# jeu_du_moulin_boura_LedMatrix_SCH.net
KiCad netlist of a schematic drawn in Altium Designer
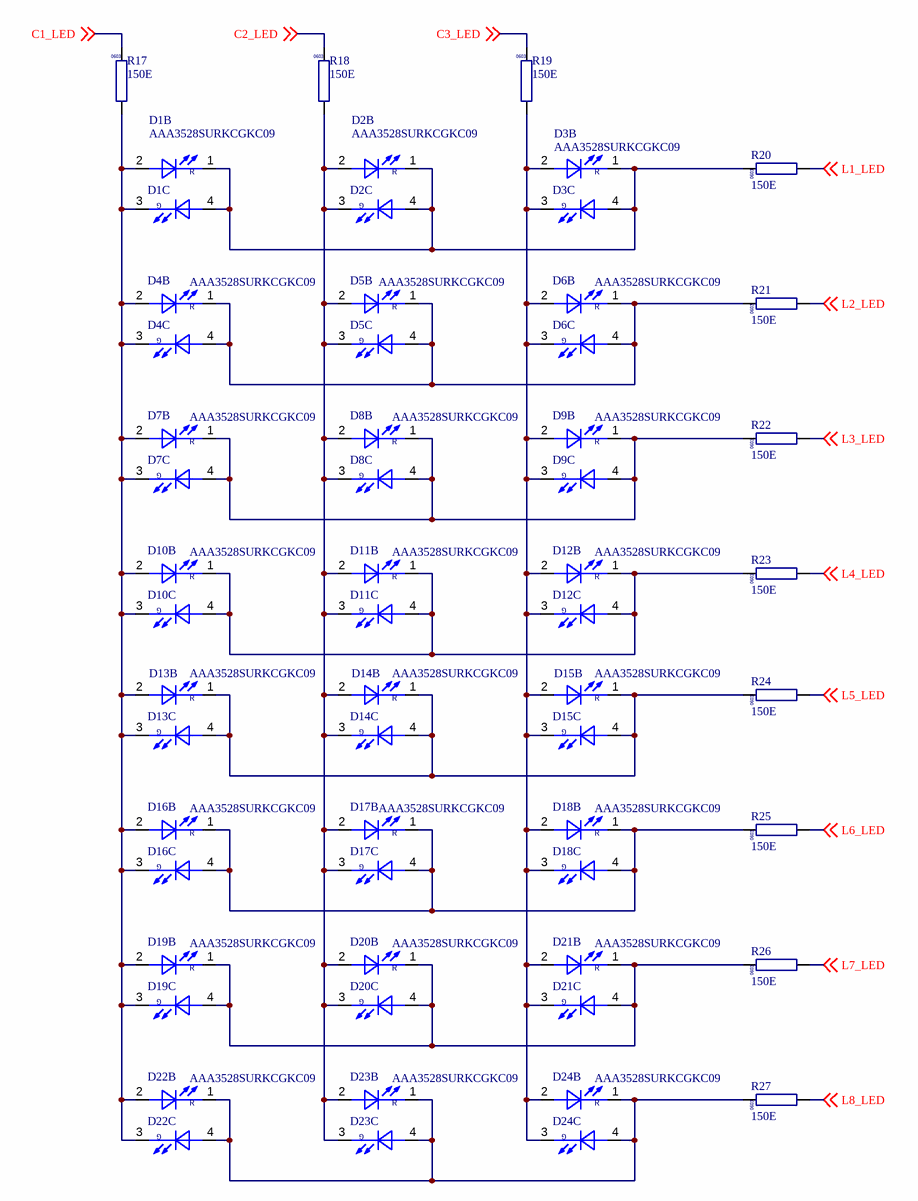
[diagram p0: jeu_du_moulin_boura_LedMatrix_SCH.SchDoc]

(export (version "E")
  (design (tool "Eeschema 10.0.6"))
  (components
    (comp (ref "D1")
      (value "AAA3528SURKCGKC09")
      (footprint "TouchPAD-8mm+LED 4-SMD CIR")
      (libsource (lib "jeu_du_moulin_boura_INTLIB") (part "TouchPAD-BILED4SMD"))
    )
    (comp (ref "D2")
      (value "AAA3528SURKCGKC09")
      (footprint "TouchPAD-8mm+LED 4-SMD CIR")
      (libsource (lib "jeu_du_moulin_boura_INTLIB") (part "TouchPAD-BILED4SMD"))
    )
    (comp (ref "D3")
      (value "AAA3528SURKCGKC09")
      (footprint "TouchPAD-8mm+LED 4-SMD CIR")
      (libsource (lib "jeu_du_moulin_boura_INTLIB") (part "TouchPAD-BILED4SMD"))
    )
    (comp (ref "D4")
      (value "AAA3528SURKCGKC09")
      (footprint "TouchPAD-8mm+LED 4-SMD CIR")
      (libsource (lib "jeu_du_moulin_boura_INTLIB") (part "TouchPAD-BILED4SMD"))
    )
    (comp (ref "D5")
      (value "AAA3528SURKCGKC09")
      (footprint "TouchPAD-8mm+LED 4-SMD CIR")
      (libsource (lib "jeu_du_moulin_boura_INTLIB") (part "TouchPAD-BILED4SMD"))
    )
    (comp (ref "D6")
      (value "AAA3528SURKCGKC09")
      (footprint "TouchPAD-8mm+LED 4-SMD CIR")
      (libsource (lib "jeu_du_moulin_boura_INTLIB") (part "TouchPAD-BILED4SMD"))
    )
    (comp (ref "D7")
      (value "AAA3528SURKCGKC09")
      (footprint "TouchPAD-8mm+LED 4-SMD CIR")
      (libsource (lib "jeu_du_moulin_boura_INTLIB") (part "TouchPAD-BILED4SMD"))
    )
    (comp (ref "D8")
      (value "AAA3528SURKCGKC09")
      (footprint "TouchPAD-8mm+LED 4-SMD CIR")
      (libsource (lib "jeu_du_moulin_boura_INTLIB") (part "TouchPAD-BILED4SMD"))
    )
    (comp (ref "D9")
      (value "AAA3528SURKCGKC09")
      (footprint "TouchPAD-8mm+LED 4-SMD CIR")
      (libsource (lib "jeu_du_moulin_boura_INTLIB") (part "TouchPAD-BILED4SMD"))
    )
    (comp (ref "D10")
      (value "AAA3528SURKCGKC09")
      (footprint "TouchPAD-8mm+LED 4-SMD CIR")
      (libsource (lib "jeu_du_moulin_boura_INTLIB") (part "TouchPAD-BILED4SMD"))
    )
    (comp (ref "D11")
      (value "AAA3528SURKCGKC09")
      (footprint "TouchPAD-8mm+LED 4-SMD CIR")
      (libsource (lib "jeu_du_moulin_boura_INTLIB") (part "TouchPAD-BILED4SMD"))
    )
    (comp (ref "D12")
      (value "AAA3528SURKCGKC09")
      (footprint "TouchPAD-8mm+LED 4-SMD CIR")
      (libsource (lib "jeu_du_moulin_boura_INTLIB") (part "TouchPAD-BILED4SMD"))
    )
    (comp (ref "D13")
      (value "AAA3528SURKCGKC09")
      (footprint "TouchPAD-8mm+LED 4-SMD CIR")
      (libsource (lib "jeu_du_moulin_boura_INTLIB") (part "TouchPAD-BILED4SMD"))
    )
    (comp (ref "D14")
      (value "AAA3528SURKCGKC09")
      (footprint "TouchPAD-8mm+LED 4-SMD CIR")
      (libsource (lib "jeu_du_moulin_boura_INTLIB") (part "TouchPAD-BILED4SMD"))
    )
    (comp (ref "D15")
      (value "AAA3528SURKCGKC09")
      (footprint "TouchPAD-8mm+LED 4-SMD CIR")
      (libsource (lib "jeu_du_moulin_boura_INTLIB") (part "TouchPAD-BILED4SMD"))
    )
    (comp (ref "D16")
      (value "AAA3528SURKCGKC09")
      (footprint "TouchPAD-8mm+LED 4-SMD CIR")
      (libsource (lib "jeu_du_moulin_boura_INTLIB") (part "TouchPAD-BILED4SMD"))
    )
    (comp (ref "D17")
      (value "AAA3528SURKCGKC09")
      (footprint "TouchPAD-8mm+LED 4-SMD CIR")
      (libsource (lib "jeu_du_moulin_boura_INTLIB") (part "TouchPAD-BILED4SMD"))
    )
    (comp (ref "D18")
      (value "AAA3528SURKCGKC09")
      (footprint "TouchPAD-8mm+LED 4-SMD CIR")
      (libsource (lib "jeu_du_moulin_boura_INTLIB") (part "TouchPAD-BILED4SMD"))
    )
    (comp (ref "D19")
      (value "AAA3528SURKCGKC09")
      (footprint "TouchPAD-8mm+LED 4-SMD CIR")
      (libsource (lib "jeu_du_moulin_boura_INTLIB") (part "TouchPAD-BILED4SMD"))
    )
    (comp (ref "D20")
      (value "AAA3528SURKCGKC09")
      (footprint "TouchPAD-8mm+LED 4-SMD CIR")
      (libsource (lib "jeu_du_moulin_boura_INTLIB") (part "TouchPAD-BILED4SMD"))
    )
    (comp (ref "D21")
      (value "AAA3528SURKCGKC09")
      (footprint "TouchPAD-8mm+LED 4-SMD CIR")
      (libsource (lib "jeu_du_moulin_boura_INTLIB") (part "TouchPAD-BILED4SMD"))
    )
    (comp (ref "D22")
      (value "AAA3528SURKCGKC09")
      (footprint "TouchPAD-8mm+LED 4-SMD CIR")
      (libsource (lib "jeu_du_moulin_boura_INTLIB") (part "TouchPAD-BILED4SMD"))
    )
    (comp (ref "D23")
      (value "AAA3528SURKCGKC09")
      (footprint "TouchPAD-8mm+LED 4-SMD CIR")
      (libsource (lib "jeu_du_moulin_boura_INTLIB") (part "TouchPAD-BILED4SMD"))
    )
    (comp (ref "D24")
      (value "AAA3528SURKCGKC09")
      (footprint "TouchPAD-8mm+LED 4-SMD CIR")
      (libsource (lib "jeu_du_moulin_boura_INTLIB") (part "TouchPAD-BILED4SMD"))
    )
    (comp (ref "R17")
      (value "150E")
      (footprint "RSMD0603")
      (description "R SMD 150E  1% 60mW  CHIP 0603")
      (fields (field (name "POWER") "60mW"))
      (libsource (lib "") (part "E_RSMD0603_1"))
    )
    (comp (ref "R18")
      (value "150E")
      (footprint "RSMD0603")
      (description "R SMD 150E  1% 60mW  CHIP 0603")
      (fields (field (name "POWER") "60mW"))
      (libsource (lib "") (part "E_RSMD0603_1"))
    )
    (comp (ref "R19")
      (value "150E")
      (footprint "RSMD0603")
      (description "R SMD 150E  1% 60mW  CHIP 0603")
      (fields (field (name "POWER") "60mW"))
      (libsource (lib "") (part "E_RSMD0603_1"))
    )
    (comp (ref "R20")
      (value "150E")
      (footprint "RSMD0603")
      (description "R SMD 150E  1% 60mW  CHIP 0603")
      (fields (field (name "POWER") "60mW"))
      (libsource (lib "EMF_DataBase") (part "E_RSMD0603"))
    )
    (comp (ref "R21")
      (value "150E")
      (footprint "RSMD0603")
      (description "R SMD 150E  1% 60mW  CHIP 0603")
      (fields (field (name "POWER") "60mW"))
      (libsource (lib "EMF_DataBase") (part "E_RSMD0603"))
    )
    (comp (ref "R22")
      (value "150E")
      (footprint "RSMD0603")
      (description "R SMD 150E  1% 60mW  CHIP 0603")
      (fields (field (name "POWER") "60mW"))
      (libsource (lib "EMF_DataBase") (part "E_RSMD0603"))
    )
    (comp (ref "R23")
      (value "150E")
      (footprint "RSMD0603")
      (description "R SMD 150E  1% 60mW  CHIP 0603")
      (fields (field (name "POWER") "60mW"))
      (libsource (lib "EMF_DataBase") (part "E_RSMD0603"))
    )
    (comp (ref "R24")
      (value "150E")
      (footprint "RSMD0603")
      (description "R SMD 150E  1% 60mW  CHIP 0603")
      (fields (field (name "POWER") "60mW"))
      (libsource (lib "EMF_DataBase") (part "E_RSMD0603"))
    )
    (comp (ref "R25")
      (value "150E")
      (footprint "RSMD0603")
      (description "R SMD 150E  1% 60mW  CHIP 0603")
      (fields (field (name "POWER") "60mW"))
      (libsource (lib "EMF_DataBase") (part "E_RSMD0603"))
    )
    (comp (ref "R26")
      (value "150E")
      (footprint "RSMD0603")
      (description "R SMD 150E  1% 60mW  CHIP 0603")
      (fields (field (name "POWER") "60mW"))
      (libsource (lib "EMF_DataBase") (part "E_RSMD0603"))
    )
    (comp (ref "R27")
      (value "150E")
      (footprint "RSMD0603")
      (description "R SMD 150E  1% 60mW  CHIP 0603")
      (fields (field (name "POWER") "60mW"))
      (libsource (lib "EMF_DataBase") (part "E_RSMD0603"))
    )
  )
  (nets
    (net (code "1") (name "C1_LED") (class "Default")
      (node (ref "R17") (pin "1") (pinfunction "1_1") (pintype "passive"))
    )
    (net (code "2") (name "C2_LED") (class "Default")
      (node (ref "R18") (pin "1") (pinfunction "1_1") (pintype "passive"))
    )
    (net (code "3") (name "C3_LED") (class "Default")
      (node (ref "R19") (pin "1") (pinfunction "1_1") (pintype "passive"))
    )
    (net (code "4") (name "L1_LED") (class "Default")
      (node (ref "R20") (pin "2") (pinfunction "2_2") (pintype "passive"))
    )
    (net (code "5") (name "L2_LED") (class "Default")
      (node (ref "R21") (pin "2") (pinfunction "2_2") (pintype "passive"))
    )
    (net (code "6") (name "L3_LED") (class "Default")
      (node (ref "R22") (pin "2") (pinfunction "2_2") (pintype "passive"))
    )
    (net (code "7") (name "L4_LED") (class "Default")
      (node (ref "R23") (pin "2") (pinfunction "2_2") (pintype "passive"))
    )
    (net (code "8") (name "L5_LED") (class "Default")
      (node (ref "R24") (pin "2") (pinfunction "2_2") (pintype "passive"))
    )
    (net (code "9") (name "L6_LED") (class "Default")
      (node (ref "R25") (pin "2") (pinfunction "2_2") (pintype "passive"))
    )
    (net (code "10") (name "L7_LED") (class "Default")
      (node (ref "R26") (pin "2") (pinfunction "2_2") (pintype "passive"))
    )
    (net (code "11") (name "L8_LED") (class "Default")
      (node (ref "R27") (pin "2") (pinfunction "2_2") (pintype "passive"))
    )
    (net (code "12") (name "Net-(D1B-CATHODE)") (class "Default")
      (node (ref "D1") (pin "1") (pinfunction "CATHODE_1") (pintype "passive"))
      (node (ref "D1") (pin "4") (pinfunction "ANODE_4") (pintype "passive"))
      (node (ref "D2") (pin "1") (pinfunction "CATHODE_1") (pintype "passive"))
      (node (ref "D2") (pin "4") (pinfunction "ANODE_4") (pintype "passive"))
      (node (ref "D3") (pin "1") (pinfunction "CATHODE_1") (pintype "passive"))
      (node (ref "D3") (pin "4") (pinfunction "ANODE_4") (pintype "passive"))
      (node (ref "R20") (pin "1") (pinfunction "1_1") (pintype "passive"))
    )
    (net (code "13") (name "Net-(D4B-CATHODE)") (class "Default")
      (node (ref "D4") (pin "1") (pinfunction "CATHODE_1") (pintype "passive"))
      (node (ref "D4") (pin "4") (pinfunction "ANODE_4") (pintype "passive"))
      (node (ref "D5") (pin "1") (pinfunction "CATHODE_1") (pintype "passive"))
      (node (ref "D5") (pin "4") (pinfunction "ANODE_4") (pintype "passive"))
      (node (ref "D6") (pin "1") (pinfunction "CATHODE_1") (pintype "passive"))
      (node (ref "D6") (pin "4") (pinfunction "ANODE_4") (pintype "passive"))
      (node (ref "R21") (pin "1") (pinfunction "1_1") (pintype "passive"))
    )
    (net (code "14") (name "Net-(D7B-CATHODE)") (class "Default")
      (node (ref "D7") (pin "1") (pinfunction "CATHODE_1") (pintype "passive"))
      (node (ref "D7") (pin "4") (pinfunction "ANODE_4") (pintype "passive"))
      (node (ref "D8") (pin "1") (pinfunction "CATHODE_1") (pintype "passive"))
      (node (ref "D8") (pin "4") (pinfunction "ANODE_4") (pintype "passive"))
      (node (ref "D9") (pin "1") (pinfunction "CATHODE_1") (pintype "passive"))
      (node (ref "D9") (pin "4") (pinfunction "ANODE_4") (pintype "passive"))
      (node (ref "R22") (pin "1") (pinfunction "1_1") (pintype "passive"))
    )
    (net (code "15") (name "Net-(D10B-ANODE)") (class "Default")
      (node (ref "D1") (pin "2") (pinfunction "ANODE_2") (pintype "passive"))
      (node (ref "D1") (pin "3") (pinfunction "CATHODE_3") (pintype "passive"))
      (node (ref "D10") (pin "2") (pinfunction "ANODE_2") (pintype "passive"))
      (node (ref "D10") (pin "3") (pinfunction "CATHODE_3") (pintype "passive"))
      (node (ref "D13") (pin "2") (pinfunction "ANODE_2") (pintype "passive"))
      (node (ref "D13") (pin "3") (pinfunction "CATHODE_3") (pintype "passive"))
      (node (ref "D16") (pin "2") (pinfunction "ANODE_2") (pintype "passive"))
      (node (ref "D16") (pin "3") (pinfunction "CATHODE_3") (pintype "passive"))
      (node (ref "D19") (pin "2") (pinfunction "ANODE_2") (pintype "passive"))
      (node (ref "D19") (pin "3") (pinfunction "CATHODE_3") (pintype "passive"))
      (node (ref "D22") (pin "2") (pinfunction "ANODE_2") (pintype "passive"))
      (node (ref "D22") (pin "3") (pinfunction "CATHODE_3") (pintype "passive"))
      (node (ref "D4") (pin "2") (pinfunction "ANODE_2") (pintype "passive"))
      (node (ref "D4") (pin "3") (pinfunction "CATHODE_3") (pintype "passive"))
      (node (ref "D7") (pin "2") (pinfunction "ANODE_2") (pintype "passive"))
      (node (ref "D7") (pin "3") (pinfunction "CATHODE_3") (pintype "passive"))
      (node (ref "R17") (pin "2") (pinfunction "2_2") (pintype "passive"))
    )
    (net (code "16") (name "Net-(D10B-CATHODE)") (class "Default")
      (node (ref "D10") (pin "1") (pinfunction "CATHODE_1") (pintype "passive"))
      (node (ref "D10") (pin "4") (pinfunction "ANODE_4") (pintype "passive"))
      (node (ref "D11") (pin "1") (pinfunction "CATHODE_1") (pintype "passive"))
      (node (ref "D11") (pin "4") (pinfunction "ANODE_4") (pintype "passive"))
      (node (ref "D12") (pin "1") (pinfunction "CATHODE_1") (pintype "passive"))
      (node (ref "D12") (pin "4") (pinfunction "ANODE_4") (pintype "passive"))
      (node (ref "R23") (pin "1") (pinfunction "1_1") (pintype "passive"))
    )
    (net (code "17") (name "Net-(D11B-ANODE)") (class "Default")
      (node (ref "D11") (pin "2") (pinfunction "ANODE_2") (pintype "passive"))
      (node (ref "D11") (pin "3") (pinfunction "CATHODE_3") (pintype "passive"))
      (node (ref "D14") (pin "2") (pinfunction "ANODE_2") (pintype "passive"))
      (node (ref "D14") (pin "3") (pinfunction "CATHODE_3") (pintype "passive"))
      (node (ref "D17") (pin "2") (pinfunction "ANODE_2") (pintype "passive"))
      (node (ref "D17") (pin "3") (pinfunction "CATHODE_3") (pintype "passive"))
      (node (ref "D2") (pin "2") (pinfunction "ANODE_2") (pintype "passive"))
      (node (ref "D2") (pin "3") (pinfunction "CATHODE_3") (pintype "passive"))
      (node (ref "D20") (pin "2") (pinfunction "ANODE_2") (pintype "passive"))
      (node (ref "D20") (pin "3") (pinfunction "CATHODE_3") (pintype "passive"))
      (node (ref "D23") (pin "2") (pinfunction "ANODE_2") (pintype "passive"))
      (node (ref "D23") (pin "3") (pinfunction "CATHODE_3") (pintype "passive"))
      (node (ref "D5") (pin "2") (pinfunction "ANODE_2") (pintype "passive"))
      (node (ref "D5") (pin "3") (pinfunction "CATHODE_3") (pintype "passive"))
      (node (ref "D8") (pin "2") (pinfunction "ANODE_2") (pintype "passive"))
      (node (ref "D8") (pin "3") (pinfunction "CATHODE_3") (pintype "passive"))
      (node (ref "R18") (pin "2") (pinfunction "2_2") (pintype "passive"))
    )
    (net (code "18") (name "Net-(D12B-ANODE)") (class "Default")
      (node (ref "D12") (pin "2") (pinfunction "ANODE_2") (pintype "passive"))
      (node (ref "D12") (pin "3") (pinfunction "CATHODE_3") (pintype "passive"))
      (node (ref "D15") (pin "2") (pinfunction "ANODE_2") (pintype "passive"))
      (node (ref "D15") (pin "3") (pinfunction "CATHODE_3") (pintype "passive"))
      (node (ref "D18") (pin "2") (pinfunction "ANODE_2") (pintype "passive"))
      (node (ref "D18") (pin "3") (pinfunction "CATHODE_3") (pintype "passive"))
      (node (ref "D21") (pin "2") (pinfunction "ANODE_2") (pintype "passive"))
      (node (ref "D21") (pin "3") (pinfunction "CATHODE_3") (pintype "passive"))
      (node (ref "D24") (pin "2") (pinfunction "ANODE_2") (pintype "passive"))
      (node (ref "D24") (pin "3") (pinfunction "CATHODE_3") (pintype "passive"))
      (node (ref "D3") (pin "2") (pinfunction "ANODE_2") (pintype "passive"))
      (node (ref "D3") (pin "3") (pinfunction "CATHODE_3") (pintype "passive"))
      (node (ref "D6") (pin "2") (pinfunction "ANODE_2") (pintype "passive"))
      (node (ref "D6") (pin "3") (pinfunction "CATHODE_3") (pintype "passive"))
      (node (ref "D9") (pin "2") (pinfunction "ANODE_2") (pintype "passive"))
      (node (ref "D9") (pin "3") (pinfunction "CATHODE_3") (pintype "passive"))
      (node (ref "R19") (pin "2") (pinfunction "2_2") (pintype "passive"))
    )
    (net (code "19") (name "Net-(D13B-CATHODE)") (class "Default")
      (node (ref "D13") (pin "1") (pinfunction "CATHODE_1") (pintype "passive"))
      (node (ref "D13") (pin "4") (pinfunction "ANODE_4") (pintype "passive"))
      (node (ref "D14") (pin "1") (pinfunction "CATHODE_1") (pintype "passive"))
      (node (ref "D14") (pin "4") (pinfunction "ANODE_4") (pintype "passive"))
      (node (ref "D15") (pin "1") (pinfunction "CATHODE_1") (pintype "passive"))
      (node (ref "D15") (pin "4") (pinfunction "ANODE_4") (pintype "passive"))
      (node (ref "R24") (pin "1") (pinfunction "1_1") (pintype "passive"))
    )
    (net (code "20") (name "Net-(D16B-CATHODE)") (class "Default")
      (node (ref "D16") (pin "1") (pinfunction "CATHODE_1") (pintype "passive"))
      (node (ref "D16") (pin "4") (pinfunction "ANODE_4") (pintype "passive"))
      (node (ref "D17") (pin "1") (pinfunction "CATHODE_1") (pintype "passive"))
      (node (ref "D17") (pin "4") (pinfunction "ANODE_4") (pintype "passive"))
      (node (ref "D18") (pin "1") (pinfunction "CATHODE_1") (pintype "passive"))
      (node (ref "D18") (pin "4") (pinfunction "ANODE_4") (pintype "passive"))
      (node (ref "R25") (pin "1") (pinfunction "1_1") (pintype "passive"))
    )
    (net (code "21") (name "Net-(D19B-CATHODE)") (class "Default")
      (node (ref "D19") (pin "1") (pinfunction "CATHODE_1") (pintype "passive"))
      (node (ref "D19") (pin "4") (pinfunction "ANODE_4") (pintype "passive"))
      (node (ref "D20") (pin "1") (pinfunction "CATHODE_1") (pintype "passive"))
      (node (ref "D20") (pin "4") (pinfunction "ANODE_4") (pintype "passive"))
      (node (ref "D21") (pin "1") (pinfunction "CATHODE_1") (pintype "passive"))
      (node (ref "D21") (pin "4") (pinfunction "ANODE_4") (pintype "passive"))
      (node (ref "R26") (pin "1") (pinfunction "1_1") (pintype "passive"))
    )
    (net (code "22") (name "Net-(D22B-CATHODE)") (class "Default")
      (node (ref "D22") (pin "1") (pinfunction "CATHODE_1") (pintype "passive"))
      (node (ref "D22") (pin "4") (pinfunction "ANODE_4") (pintype "passive"))
      (node (ref "D23") (pin "1") (pinfunction "CATHODE_1") (pintype "passive"))
      (node (ref "D23") (pin "4") (pinfunction "ANODE_4") (pintype "passive"))
      (node (ref "D24") (pin "1") (pinfunction "CATHODE_1") (pintype "passive"))
      (node (ref "D24") (pin "4") (pinfunction "ANODE_4") (pintype "passive"))
      (node (ref "R27") (pin "1") (pinfunction "1_1") (pintype "passive"))
    )
  )
)
